# EXT-PHY.net
KiCad netlist of a schematic drawn in EAGLE
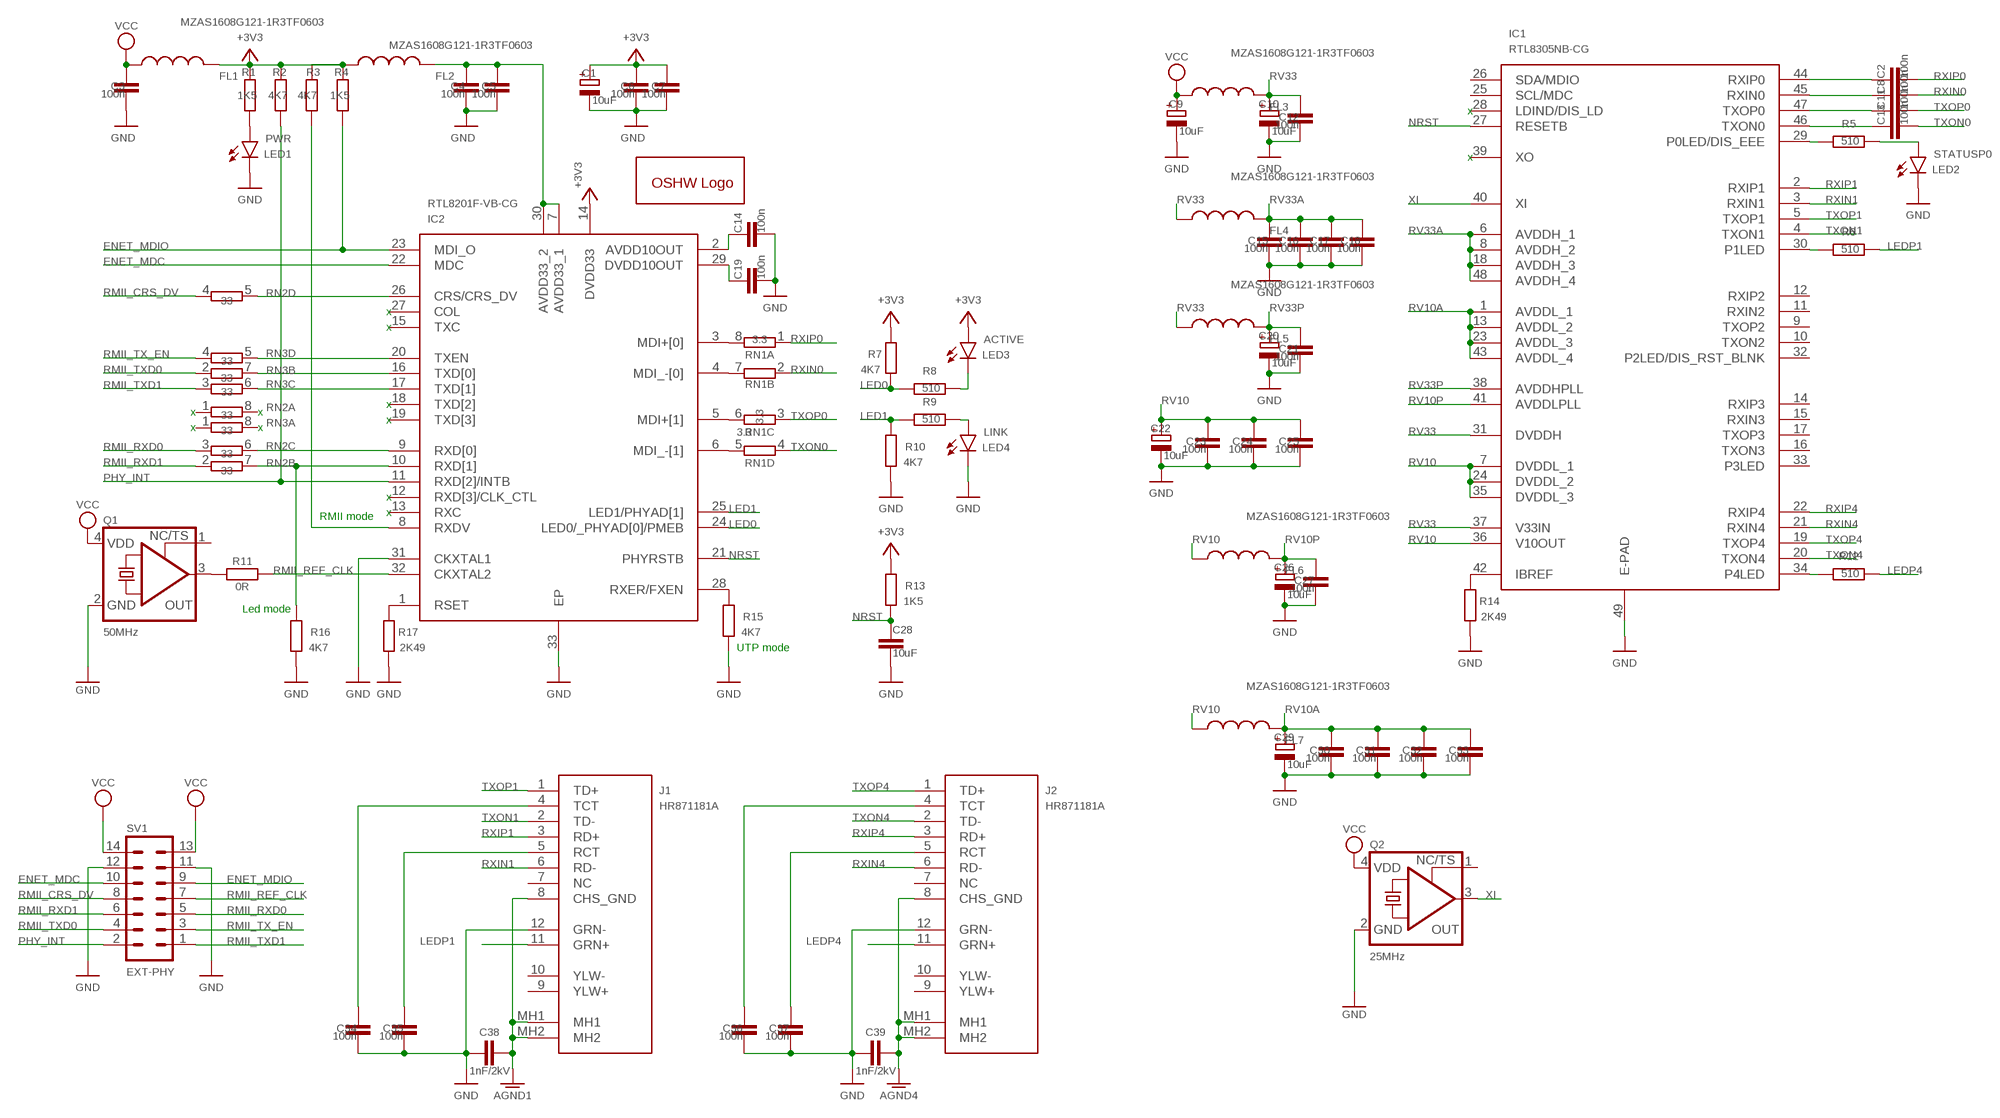
[diagram p0: schematic, sheet 1]

(export (version "E")
  (design (tool "Eeschema 10.0.6"))
  (components
    (comp (ref "C1")
      (value "10uF")
      (footprint "eagle-import:A_3216-18R")
      (libsource (lib "eagle-import") (part "CPOL-EUA/3216-18R"))
    )
    (comp (ref "C2")
      (value "100n")
      (footprint "eagle-import:C0402")
      (libsource (lib "eagle-import") (part "C-EUC0402"))
    )
    (comp (ref "C3")
      (value "100n")
      (footprint "eagle-import:C0402")
      (libsource (lib "eagle-import") (part "C-EUC0402"))
    )
    (comp (ref "C4")
      (value "100n")
      (footprint "eagle-import:C0402")
      (libsource (lib "eagle-import") (part "C-EUC0402"))
    )
    (comp (ref "C5")
      (value "100n")
      (footprint "eagle-import:C0402")
      (libsource (lib "eagle-import") (part "C-EUC0402"))
    )
    (comp (ref "C6")
      (value "100n")
      (footprint "eagle-import:C0402")
      (libsource (lib "eagle-import") (part "C-EUC0402"))
    )
    (comp (ref "C7")
      (value "100n")
      (footprint "eagle-import:C0402")
      (libsource (lib "eagle-import") (part "C-EUC0402"))
    )
    (comp (ref "C8")
      (value "100n")
      (footprint "eagle-import:C0402")
      (libsource (lib "eagle-import") (part "C-EUC0402"))
    )
    (comp (ref "C9")
      (value "10uF")
      (footprint "eagle-import:A_3216-18R")
      (libsource (lib "eagle-import") (part "CPOL-EUA/3216-18R"))
    )
    (comp (ref "C10")
      (value "10uF")
      (footprint "eagle-import:A_3216-18R")
      (libsource (lib "eagle-import") (part "CPOL-EUA/3216-18R"))
    )
    (comp (ref "C11")
      (value "100n")
      (footprint "eagle-import:C0402")
      (libsource (lib "eagle-import") (part "C-EUC0402"))
    )
    (comp (ref "C12")
      (value "100n")
      (footprint "eagle-import:C0402")
      (libsource (lib "eagle-import") (part "C-EUC0402"))
    )
    (comp (ref "C13")
      (value "100n")
      (footprint "eagle-import:C0402")
      (libsource (lib "eagle-import") (part "C-EUC0402"))
    )
    (comp (ref "C14")
      (value "100n")
      (footprint "eagle-import:C0402")
      (libsource (lib "eagle-import") (part "C-EUC0402"))
    )
    (comp (ref "C15")
      (value "100n")
      (footprint "eagle-import:C0402")
      (libsource (lib "eagle-import") (part "C-EUC0402"))
    )
    (comp (ref "C16")
      (value "100n")
      (footprint "eagle-import:C0402")
      (libsource (lib "eagle-import") (part "C-EUC0402"))
    )
    (comp (ref "C17")
      (value "100n")
      (footprint "eagle-import:C0402")
      (libsource (lib "eagle-import") (part "C-EUC0402"))
    )
    (comp (ref "C18")
      (value "100n")
      (footprint "eagle-import:C0402")
      (libsource (lib "eagle-import") (part "C-EUC0402"))
    )
    (comp (ref "C19")
      (value "100n")
      (footprint "eagle-import:C0402")
      (libsource (lib "eagle-import") (part "C-EUC0402"))
    )
    (comp (ref "C20")
      (value "10uF")
      (footprint "eagle-import:A_3216-18R")
      (libsource (lib "eagle-import") (part "CPOL-EUA/3216-18R"))
    )
    (comp (ref "C21")
      (value "100n")
      (footprint "eagle-import:C0402")
      (libsource (lib "eagle-import") (part "C-EUC0402"))
    )
    (comp (ref "C22")
      (value "10uF")
      (footprint "eagle-import:A_3216-18R")
      (libsource (lib "eagle-import") (part "CPOL-EUA/3216-18R"))
    )
    (comp (ref "C23")
      (value "100n")
      (footprint "eagle-import:C0402")
      (libsource (lib "eagle-import") (part "C-EUC0402"))
    )
    (comp (ref "C24")
      (value "100n")
      (footprint "eagle-import:C0402")
      (libsource (lib "eagle-import") (part "C-EUC0402"))
    )
    (comp (ref "C25")
      (value "100n")
      (footprint "eagle-import:C0402")
      (libsource (lib "eagle-import") (part "C-EUC0402"))
    )
    (comp (ref "C26")
      (value "10uF")
      (footprint "eagle-import:A_3216-18R")
      (libsource (lib "eagle-import") (part "CPOL-EUA/3216-18R"))
    )
    (comp (ref "C27")
      (value "100n")
      (footprint "eagle-import:C0402")
      (libsource (lib "eagle-import") (part "C-EUC0402"))
    )
    (comp (ref "C28")
      (value "10uF")
      (footprint "eagle-import:C0603")
      (libsource (lib "eagle-import") (part "C-EUC0603"))
    )
    (comp (ref "C29")
      (value "10uF")
      (footprint "eagle-import:A_3216-18R")
      (libsource (lib "eagle-import") (part "CPOL-EUA/3216-18R"))
    )
    (comp (ref "C30")
      (value "100n")
      (footprint "eagle-import:C0402")
      (libsource (lib "eagle-import") (part "C-EUC0402"))
    )
    (comp (ref "C31")
      (value "100n")
      (footprint "eagle-import:C0402")
      (libsource (lib "eagle-import") (part "C-EUC0402"))
    )
    (comp (ref "C32")
      (value "100n")
      (footprint "eagle-import:C0402")
      (libsource (lib "eagle-import") (part "C-EUC0402"))
    )
    (comp (ref "C33")
      (value "100n")
      (footprint "eagle-import:C0402")
      (libsource (lib "eagle-import") (part "C-EUC0402"))
    )
    (comp (ref "C34")
      (value "100n")
      (footprint "eagle-import:C0402")
      (libsource (lib "eagle-import") (part "C-EUC0402"))
    )
    (comp (ref "C35")
      (value "100n")
      (footprint "eagle-import:C0402")
      (libsource (lib "eagle-import") (part "C-EUC0402"))
    )
    (comp (ref "C36")
      (value "100n")
      (footprint "eagle-import:C0402")
      (libsource (lib "eagle-import") (part "C-EUC0402"))
    )
    (comp (ref "C37")
      (value "100n")
      (footprint "eagle-import:C0402")
      (libsource (lib "eagle-import") (part "C-EUC0402"))
    )
    (comp (ref "C38")
      (value "1nF/2kV")
      (footprint "eagle-import:C1206")
      (fields (field (name "SPICEPREFIX") "C"))
      (libsource (lib "eagle-import") (part "C-EUC1206"))
    )
    (comp (ref "C39")
      (value "1nF/2kV")
      (footprint "eagle-import:C1206")
      (fields (field (name "SPICEPREFIX") "C"))
      (libsource (lib "eagle-import") (part "C-EUC1206"))
    )
    (comp (ref "FL1")
      (value "MZAS1608G121-1R3TF0603")
      (footprint "eagle-import:0603")
      (libsource (lib "eagle-import") (part "MZAS1608G121-1R3TF0603"))
    )
    (comp (ref "FL2")
      (value "MZAS1608G121-1R3TF0603")
      (footprint "eagle-import:0603")
      (libsource (lib "eagle-import") (part "MZAS1608G121-1R3TF0603"))
    )
    (comp (ref "FL3")
      (value "MZAS1608G121-1R3TF0603")
      (footprint "eagle-import:0603")
      (libsource (lib "eagle-import") (part "MZAS1608G121-1R3TF0603"))
    )
    (comp (ref "FL4")
      (value "MZAS1608G121-1R3TF0603")
      (footprint "eagle-import:0603")
      (libsource (lib "eagle-import") (part "MZAS1608G121-1R3TF0603"))
    )
    (comp (ref "FL5")
      (value "MZAS1608G121-1R3TF0603")
      (footprint "eagle-import:0603")
      (libsource (lib "eagle-import") (part "MZAS1608G121-1R3TF0603"))
    )
    (comp (ref "FL6")
      (value "MZAS1608G121-1R3TF0603")
      (footprint "eagle-import:0603")
      (libsource (lib "eagle-import") (part "MZAS1608G121-1R3TF0603"))
    )
    (comp (ref "FL7")
      (value "MZAS1608G121-1R3TF0603")
      (footprint "eagle-import:0603")
      (libsource (lib "eagle-import") (part "MZAS1608G121-1R3TF0603"))
    )
    (comp (ref "GOLD_ORB_SM1")
      (value "OSHWLOGOLOGO5MM")
      (footprint "eagle-import:OSHW_5MM")
      (libsource (lib "eagle-import") (part "OSHWLOGOLOGO5MM"))
    )
    (comp (ref "IC1")
      (value "RTL8305NB-CG")
      (footprint "eagle-import:QFN40P600X600X100-49N")
      (libsource (lib "eagle-import") (part "RTL8305NB-CG"))
    )
    (comp (ref "IC2")
      (value "RTL8201F-VB-CG")
      (footprint "eagle-import:QFN50P500X500X100-33N")
      (fields (field (name "JLCPCB") "C45044"))
      (libsource (lib "eagle-import") (part "RTL8201F-VB-CG"))
    )
    (comp (ref "J1")
      (value "HR871181A")
      (footprint "eagle-import:HR871181A")
      (libsource (lib "eagle-import") (part "HR871181A"))
    )
    (comp (ref "J2")
      (value "HR871181A")
      (footprint "eagle-import:HR871181A")
      (libsource (lib "eagle-import") (part "HR871181A"))
    )
    (comp (ref "LED1")
      (value "PWR")
      (footprint "eagle-import:CHIP-LED0603")
      (libsource (lib "eagle-import") (part "LEDCHIP-LED0603"))
    )
    (comp (ref "LED2")
      (value "STATUSP0")
      (footprint "eagle-import:CHIP-LED0603")
      (libsource (lib "eagle-import") (part "LEDCHIP-LED0603"))
    )
    (comp (ref "LED3")
      (value "ACTIVE")
      (footprint "eagle-import:CHIP-LED0603")
      (libsource (lib "eagle-import") (part "LEDCHIP-LED0603"))
    )
    (comp (ref "LED4")
      (value "LINK")
      (footprint "eagle-import:CHIP-LED0603")
      (libsource (lib "eagle-import") (part "LEDCHIP-LED0603"))
    )
    (comp (ref "Q1")
      (value "50MHz")
      (footprint "eagle-import:3.2X2.5_KXO-V96")
      (libsource (lib "eagle-import") (part "KXO-PXO/XO-V96"))
    )
    (comp (ref "Q2")
      (value "25MHz")
      (footprint "eagle-import:3.2X2.5_KXO-V96")
      (libsource (lib "eagle-import") (part "KXO-PXO/XO-V96"))
    )
    (comp (ref "R1")
      (value "1K5")
      (footprint "eagle-import:R0603")
      (libsource (lib "eagle-import") (part "R-EU_R0603"))
    )
    (comp (ref "R2")
      (value "4K7")
      (footprint "eagle-import:R0603")
      (libsource (lib "eagle-import") (part "R-EU_R0603"))
    )
    (comp (ref "R3")
      (value "4K7")
      (footprint "eagle-import:R0603")
      (libsource (lib "eagle-import") (part "R-EU_R0603"))
    )
    (comp (ref "R4")
      (value "1K5")
      (footprint "eagle-import:R0603")
      (libsource (lib "eagle-import") (part "R-EU_R0603"))
    )
    (comp (ref "R5")
      (value "510")
      (footprint "eagle-import:R0603")
      (libsource (lib "eagle-import") (part "R-EU_R0603"))
    )
    (comp (ref "R6")
      (value "510")
      (footprint "eagle-import:R0603")
      (libsource (lib "eagle-import") (part "R-EU_R0603"))
    )
    (comp (ref "R7")
      (value "4K7")
      (footprint "eagle-import:R0603")
      (libsource (lib "eagle-import") (part "R-EU_R0603"))
    )
    (comp (ref "R8")
      (value "510")
      (footprint "eagle-import:R0603")
      (libsource (lib "eagle-import") (part "R-EU_R0603"))
    )
    (comp (ref "R9")
      (value "510")
      (footprint "eagle-import:R0603")
      (libsource (lib "eagle-import") (part "R-EU_R0603"))
    )
    (comp (ref "R10")
      (value "4K7")
      (footprint "eagle-import:R0603")
      (libsource (lib "eagle-import") (part "R-EU_R0603"))
    )
    (comp (ref "R11")
      (value "0R")
      (footprint "eagle-import:R0603")
      (libsource (lib "eagle-import") (part "R-EU_R0603"))
    )
    (comp (ref "R12")
      (value "510")
      (footprint "eagle-import:R0603")
      (libsource (lib "eagle-import") (part "R-EU_R0603"))
    )
    (comp (ref "R13")
      (value "1K5")
      (footprint "eagle-import:R0603")
      (libsource (lib "eagle-import") (part "R-EU_R0603"))
    )
    (comp (ref "R14")
      (value "2K49")
      (footprint "eagle-import:R0603")
      (libsource (lib "eagle-import") (part "R-EU_R0603"))
    )
    (comp (ref "R15")
      (value "4K7")
      (footprint "eagle-import:R0603")
      (libsource (lib "eagle-import") (part "R-EU_R0603"))
    )
    (comp (ref "R16")
      (value "4K7")
      (footprint "eagle-import:R0603")
      (libsource (lib "eagle-import") (part "R-EU_R0603"))
    )
    (comp (ref "R17")
      (value "2K49")
      (footprint "eagle-import:R0603")
      (libsource (lib "eagle-import") (part "R-EU_R0603"))
    )
    (comp (ref "RN1")
      (value "3.3")
      (footprint "eagle-import:4X0402ARV341")
      (fields (field (name "JLCPCB") "C728736"))
      (libsource (lib "eagle-import") (part "4R-N0402ARV341"))
    )
    (comp (ref "RN2")
      (value "33")
      (footprint "eagle-import:4X0402ARV341")
      (fields (field (name "JLCPCB") "C25501"))
      (libsource (lib "eagle-import") (part "4R-N0402ARV341"))
    )
    (comp (ref "RN3")
      (value "33")
      (footprint "eagle-import:4X0402ARV341")
      (fields (field (name "JLCPCB") "C25501"))
      (libsource (lib "eagle-import") (part "4R-N0402ARV341"))
    )
    (comp (ref "SV1")
      (value "EXT-PHY")
      (footprint "eagle-import:MA07-2W")
      (libsource (lib "eagle-import") (part "MA07-2W"))
    )
  )
  (nets
    (net (code "1") (name "+3V3") (class "Default")
      (node (ref "C1") (pin "+") (pinfunction "+_+") (pintype "passive"))
      (node (ref "C6") (pin "2") (pinfunction "2_2") (pintype "passive"))
      (node (ref "C7") (pin "2") (pinfunction "2_2") (pintype "passive"))
      (node (ref "FL1") (pin "2") (pinfunction "2_2") (pintype "passive"))
      (node (ref "FL2") (pin "1") (pinfunction "1_1") (pintype "passive"))
      (node (ref "IC2") (pin "14") (pinfunction "DVDD33_14") (pintype "bidirectional"))
      (node (ref "LED3") (pin "A") (pinfunction "A_A") (pintype "passive"))
      (node (ref "R1") (pin "2") (pinfunction "2_2") (pintype "passive"))
      (node (ref "R13") (pin "2") (pinfunction "2_2") (pintype "passive"))
      (node (ref "R2") (pin "2") (pinfunction "2_2") (pintype "passive"))
      (node (ref "R3") (pin "1") (pinfunction "1_1") (pintype "passive"))
      (node (ref "R4") (pin "2") (pinfunction "2_2") (pintype "passive"))
      (node (ref "R7") (pin "2") (pinfunction "2_2") (pintype "passive"))
    )
    (net (code "2") (name "/ENET_MDC") (class "Default")
      (node (ref "IC2") (pin "22") (pinfunction "MDC_22") (pintype "bidirectional"))
      (node (ref "SV1") (pin "10") (pinfunction "10_10") (pintype "passive"))
    )
    (net (code "3") (name "/ENET_MDIO") (class "Default")
      (node (ref "IC2") (pin "23") (pinfunction "MDI_O_23") (pintype "bidirectional"))
      (node (ref "R4") (pin "1") (pinfunction "1_1") (pintype "passive"))
      (node (ref "SV1") (pin "9") (pinfunction "9_9") (pintype "passive"))
    )
    (net (code "4") (name "/LED0") (class "Default")
      (node (ref "IC2") (pin "24") (pinfunction "LED0/_PHYAD[0]/PMEB_24") (pintype "bidirectional"))
      (node (ref "R7") (pin "1") (pinfunction "1_1") (pintype "passive"))
      (node (ref "R8") (pin "2") (pinfunction "2_2") (pintype "passive"))
    )
    (net (code "5") (name "/LED1") (class "Default")
      (node (ref "IC2") (pin "25") (pinfunction "LED1/PHYAD[1]_25") (pintype "bidirectional"))
      (node (ref "R10") (pin "2") (pinfunction "2_2") (pintype "passive"))
      (node (ref "R9") (pin "2") (pinfunction "2_2") (pintype "passive"))
    )
    (net (code "6") (name "/LEDP1") (class "Default")
      (node (ref "J1") (pin "11") (pinfunction "GRN+_11") (pintype "bidirectional"))
      (node (ref "R6") (pin "1") (pinfunction "1_1") (pintype "passive"))
    )
    (net (code "7") (name "/LEDP4") (class "Default")
      (node (ref "J2") (pin "11") (pinfunction "GRN+_11") (pintype "bidirectional"))
      (node (ref "R12") (pin "1") (pinfunction "1_1") (pintype "passive"))
    )
    (net (code "8") (name "/NRST") (class "Default")
      (node (ref "C28") (pin "1") (pinfunction "1_1") (pintype "passive"))
      (node (ref "IC1") (pin "27") (pinfunction "RESETB_27") (pintype "input"))
      (node (ref "IC2") (pin "21") (pinfunction "PHYRSTB_21") (pintype "bidirectional"))
      (node (ref "R13") (pin "1") (pinfunction "1_1") (pintype "passive"))
    )
    (net (code "9") (name "/PHY_INT") (class "Default")
      (node (ref "IC2") (pin "11") (pinfunction "RXD[2]/INTB_11") (pintype "bidirectional"))
      (node (ref "R2") (pin "1") (pinfunction "1_1") (pintype "passive"))
      (node (ref "SV1") (pin "2") (pinfunction "2_2") (pintype "passive"))
    )
    (net (code "10") (name "/RMII_CRS_DV") (class "Default")
      (node (ref "RN2") (pin "4") (pinfunction "1_4") (pintype "passive"))
      (node (ref "SV1") (pin "8") (pinfunction "8_8") (pintype "passive"))
    )
    (net (code "11") (name "/RMII_REF_CLK") (class "Default")
      (node (ref "IC2") (pin "32") (pinfunction "CKXTAL2_32") (pintype "bidirectional"))
      (node (ref "R11") (pin "2") (pinfunction "2_2") (pintype "passive"))
      (node (ref "SV1") (pin "7") (pinfunction "7_7") (pintype "passive"))
    )
    (net (code "12") (name "/RMII_RXD0") (class "Default")
      (node (ref "RN2") (pin "3") (pinfunction "1_3") (pintype "passive"))
      (node (ref "SV1") (pin "5") (pinfunction "5_5") (pintype "passive"))
    )
    (net (code "13") (name "/RMII_RXD1") (class "Default")
      (node (ref "RN2") (pin "2") (pinfunction "1_2") (pintype "passive"))
      (node (ref "SV1") (pin "6") (pinfunction "6_6") (pintype "passive"))
    )
    (net (code "14") (name "/RMII_TXD0") (class "Default")
      (node (ref "RN3") (pin "2") (pinfunction "1_2") (pintype "passive"))
      (node (ref "SV1") (pin "4") (pinfunction "4_4") (pintype "passive"))
    )
    (net (code "15") (name "/RMII_TXD1") (class "Default")
      (node (ref "RN3") (pin "3") (pinfunction "1_3") (pintype "passive"))
      (node (ref "SV1") (pin "1") (pinfunction "1_1") (pintype "passive"))
    )
    (net (code "16") (name "/RMII_TX_EN") (class "Default")
      (node (ref "RN3") (pin "4") (pinfunction "1_4") (pintype "passive"))
      (node (ref "SV1") (pin "3") (pinfunction "3_3") (pintype "passive"))
    )
    (net (code "17") (name "/RV10") (class "Default")
      (node (ref "C22") (pin "+") (pinfunction "+_+") (pintype "passive"))
      (node (ref "C23") (pin "2") (pinfunction "2_2") (pintype "passive"))
      (node (ref "C24") (pin "2") (pinfunction "2_2") (pintype "passive"))
      (node (ref "C25") (pin "2") (pinfunction "2_2") (pintype "passive"))
      (node (ref "FL6") (pin "1") (pinfunction "1_1") (pintype "passive"))
      (node (ref "FL7") (pin "1") (pinfunction "1_1") (pintype "passive"))
      (node (ref "IC1") (pin "24") (pinfunction "DVDDL_2_24") (pintype "power_in"))
      (node (ref "IC1") (pin "35") (pinfunction "DVDDL_3_35") (pintype "power_in"))
      (node (ref "IC1") (pin "36") (pinfunction "V10OUT_36") (pintype "power_in"))
      (node (ref "IC1") (pin "7") (pinfunction "DVDDL_1_7") (pintype "power_in"))
    )
    (net (code "18") (name "/RV10A") (class "Default")
      (node (ref "C29") (pin "+") (pinfunction "+_+") (pintype "passive"))
      (node (ref "C30") (pin "2") (pinfunction "2_2") (pintype "passive"))
      (node (ref "C31") (pin "2") (pinfunction "2_2") (pintype "passive"))
      (node (ref "C32") (pin "2") (pinfunction "2_2") (pintype "passive"))
      (node (ref "C33") (pin "2") (pinfunction "2_2") (pintype "passive"))
      (node (ref "FL7") (pin "2") (pinfunction "2_2") (pintype "passive"))
      (node (ref "IC1") (pin "1") (pinfunction "AVDDL_1_1") (pintype "power_in"))
      (node (ref "IC1") (pin "13") (pinfunction "AVDDL_2_13") (pintype "power_in"))
      (node (ref "IC1") (pin "23") (pinfunction "AVDDL_3_23") (pintype "power_in"))
      (node (ref "IC1") (pin "43") (pinfunction "AVDDL_4_43") (pintype "power_in"))
    )
    (net (code "19") (name "/RV10P") (class "Default")
      (node (ref "C26") (pin "+") (pinfunction "+_+") (pintype "passive"))
      (node (ref "C27") (pin "2") (pinfunction "2_2") (pintype "passive"))
      (node (ref "FL6") (pin "2") (pinfunction "2_2") (pintype "passive"))
      (node (ref "IC1") (pin "41") (pinfunction "AVDDLPLL_41") (pintype "power_in"))
    )
    (net (code "20") (name "/RV33") (class "Default")
      (node (ref "C10") (pin "+") (pinfunction "+_+") (pintype "passive"))
      (node (ref "C12") (pin "2") (pinfunction "2_2") (pintype "passive"))
      (node (ref "FL3") (pin "2") (pinfunction "2_2") (pintype "passive"))
      (node (ref "FL4") (pin "1") (pinfunction "1_1") (pintype "passive"))
      (node (ref "FL5") (pin "1") (pinfunction "1_1") (pintype "passive"))
      (node (ref "IC1") (pin "31") (pinfunction "DVDDH_31") (pintype "power_in"))
      (node (ref "IC1") (pin "37") (pinfunction "V33IN_37") (pintype "power_in"))
    )
    (net (code "21") (name "/RV33A") (class "Default")
      (node (ref "C15") (pin "2") (pinfunction "2_2") (pintype "passive"))
      (node (ref "C16") (pin "2") (pinfunction "2_2") (pintype "passive"))
      (node (ref "C17") (pin "2") (pinfunction "2_2") (pintype "passive"))
      (node (ref "C18") (pin "2") (pinfunction "2_2") (pintype "passive"))
      (node (ref "FL4") (pin "2") (pinfunction "2_2") (pintype "passive"))
      (node (ref "IC1") (pin "18") (pinfunction "AVDDH_3_18") (pintype "power_in"))
      (node (ref "IC1") (pin "48") (pinfunction "AVDDH_4_48") (pintype "power_in"))
      (node (ref "IC1") (pin "6") (pinfunction "AVDDH_1_6") (pintype "power_in"))
      (node (ref "IC1") (pin "8") (pinfunction "AVDDH_2_8") (pintype "power_in"))
    )
    (net (code "22") (name "/RV33P") (class "Default")
      (node (ref "C20") (pin "+") (pinfunction "+_+") (pintype "passive"))
      (node (ref "C21") (pin "2") (pinfunction "2_2") (pintype "passive"))
      (node (ref "FL5") (pin "2") (pinfunction "2_2") (pintype "passive"))
      (node (ref "IC1") (pin "38") (pinfunction "AVDDHPLL_38") (pintype "power_in"))
    )
    (net (code "23") (name "/RXIN0") (class "Default")
      (node (ref "C8") (pin "2") (pinfunction "2_2") (pintype "passive"))
      (node (ref "RN1") (pin "2") (pinfunction "1_2") (pintype "passive"))
    )
    (net (code "24") (name "/RXIN1") (class "Default")
      (node (ref "IC1") (pin "3") (pinfunction "RXIN1_3") (pintype "input"))
      (node (ref "J1") (pin "6") (pinfunction "RD-_6") (pintype "bidirectional"))
    )
    (net (code "25") (name "/RXIN4") (class "Default")
      (node (ref "IC1") (pin "21") (pinfunction "RXIN4_21") (pintype "input"))
      (node (ref "J2") (pin "6") (pinfunction "RD-_6") (pintype "bidirectional"))
    )
    (net (code "26") (name "/RXIP0") (class "Default")
      (node (ref "C2") (pin "2") (pinfunction "2_2") (pintype "passive"))
      (node (ref "RN1") (pin "1") (pinfunction "1_1") (pintype "passive"))
    )
    (net (code "27") (name "/RXIP1") (class "Default")
      (node (ref "IC1") (pin "2") (pinfunction "RXIP1_2") (pintype "input"))
      (node (ref "J1") (pin "3") (pinfunction "RD+_3") (pintype "bidirectional"))
    )
    (net (code "28") (name "/RXIP4") (class "Default")
      (node (ref "IC1") (pin "22") (pinfunction "RXIP4_22") (pintype "input"))
      (node (ref "J2") (pin "3") (pinfunction "RD+_3") (pintype "bidirectional"))
    )
    (net (code "29") (name "/TXON0") (class "Default")
      (node (ref "C13") (pin "2") (pinfunction "2_2") (pintype "passive"))
      (node (ref "RN1") (pin "4") (pinfunction "1_4") (pintype "passive"))
    )
    (net (code "30") (name "/TXON1") (class "Default")
      (node (ref "IC1") (pin "4") (pinfunction "TXON1_4") (pintype "output"))
      (node (ref "J1") (pin "2") (pinfunction "TD-_2") (pintype "bidirectional"))
    )
    (net (code "31") (name "/TXON4") (class "Default")
      (node (ref "IC1") (pin "20") (pinfunction "TXON4_20") (pintype "output"))
      (node (ref "J2") (pin "2") (pinfunction "TD-_2") (pintype "bidirectional"))
    )
    (net (code "32") (name "/TXOP0") (class "Default")
      (node (ref "C11") (pin "2") (pinfunction "2_2") (pintype "passive"))
      (node (ref "RN1") (pin "3") (pinfunction "1_3") (pintype "passive"))
    )
    (net (code "33") (name "/TXOP1") (class "Default")
      (node (ref "IC1") (pin "5") (pinfunction "TXOP1_5") (pintype "output"))
      (node (ref "J1") (pin "1") (pinfunction "TD+_1") (pintype "bidirectional"))
    )
    (net (code "34") (name "/TXOP4") (class "Default")
      (node (ref "IC1") (pin "19") (pinfunction "TXOP4_19") (pintype "output"))
      (node (ref "J2") (pin "1") (pinfunction "TD+_1") (pintype "bidirectional"))
    )
    (net (code "35") (name "/XI") (class "Default")
      (node (ref "IC1") (pin "40") (pinfunction "XI_40") (pintype "input"))
      (node (ref "Q2") (pin "3") (pinfunction "OUT_3") (pintype "output"))
    )
    (net (code "36") (name "AGND1") (class "Default")
      (node (ref "C38") (pin "2") (pinfunction "2_2") (pintype "passive"))
      (node (ref "J1") (pin "8") (pinfunction "CHS_GND_8") (pintype "bidirectional"))
      (node (ref "J1") (pin "MH1") (pinfunction "MH1_MH1") (pintype "bidirectional"))
      (node (ref "J1") (pin "MH2") (pinfunction "MH2_MH2") (pintype "bidirectional"))
    )
    (net (code "37") (name "AGND4") (class "Default")
      (node (ref "C39") (pin "2") (pinfunction "2_2") (pintype "passive"))
      (node (ref "J2") (pin "8") (pinfunction "CHS_GND_8") (pintype "bidirectional"))
      (node (ref "J2") (pin "MH1") (pinfunction "MH1_MH1") (pintype "bidirectional"))
      (node (ref "J2") (pin "MH2") (pinfunction "MH2_MH2") (pintype "bidirectional"))
    )
    (net (code "38") (name "GND") (class "Default")
      (node (ref "C1") (pin "-") (pinfunction "-_-") (pintype "passive"))
      (node (ref "C10") (pin "-") (pinfunction "-_-") (pintype "passive"))
      (node (ref "C12") (pin "1") (pinfunction "1_1") (pintype "passive"))
      (node (ref "C14") (pin "2") (pinfunction "2_2") (pintype "passive"))
      (node (ref "C15") (pin "1") (pinfunction "1_1") (pintype "passive"))
      (node (ref "C16") (pin "1") (pinfunction "1_1") (pintype "passive"))
      (node (ref "C17") (pin "1") (pinfunction "1_1") (pintype "passive"))
      (node (ref "C18") (pin "1") (pinfunction "1_1") (pintype "passive"))
      (node (ref "C19") (pin "2") (pinfunction "2_2") (pintype "passive"))
      (node (ref "C20") (pin "-") (pinfunction "-_-") (pintype "passive"))
      (node (ref "C21") (pin "1") (pinfunction "1_1") (pintype "passive"))
      (node (ref "C22") (pin "-") (pinfunction "-_-") (pintype "passive"))
      (node (ref "C23") (pin "1") (pinfunction "1_1") (pintype "passive"))
      (node (ref "C24") (pin "1") (pinfunction "1_1") (pintype "passive"))
      (node (ref "C25") (pin "1") (pinfunction "1_1") (pintype "passive"))
      (node (ref "C26") (pin "-") (pinfunction "-_-") (pintype "passive"))
      (node (ref "C27") (pin "1") (pinfunction "1_1") (pintype "passive"))
      (node (ref "C28") (pin "2") (pinfunction "2_2") (pintype "passive"))
      (node (ref "C29") (pin "-") (pinfunction "-_-") (pintype "passive"))
      (node (ref "C3") (pin "1") (pinfunction "1_1") (pintype "passive"))
      (node (ref "C30") (pin "1") (pinfunction "1_1") (pintype "passive"))
      (node (ref "C31") (pin "1") (pinfunction "1_1") (pintype "passive"))
      (node (ref "C32") (pin "1") (pinfunction "1_1") (pintype "passive"))
      (node (ref "C33") (pin "1") (pinfunction "1_1") (pintype "passive"))
      (node (ref "C34") (pin "1") (pinfunction "1_1") (pintype "passive"))
      (node (ref "C35") (pin "1") (pinfunction "1_1") (pintype "passive"))
      (node (ref "C36") (pin "1") (pinfunction "1_1") (pintype "passive"))
      (node (ref "C37") (pin "1") (pinfunction "1_1") (pintype "passive"))
      (node (ref "C38") (pin "1") (pinfunction "1_1") (pintype "passive"))
      (node (ref "C39") (pin "1") (pinfunction "1_1") (pintype "passive"))
      (node (ref "C4") (pin "1") (pinfunction "1_1") (pintype "passive"))
      (node (ref "C5") (pin "1") (pinfunction "1_1") (pintype "passive"))
      (node (ref "C6") (pin "1") (pinfunction "1_1") (pintype "passive"))
      (node (ref "C7") (pin "1") (pinfunction "1_1") (pintype "passive"))
      (node (ref "C9") (pin "-") (pinfunction "-_-") (pintype "passive"))
      (node (ref "IC1") (pin "49") (pinfunction "E-PAD_49") (pintype "power_in"))
      (node (ref "IC2") (pin "31") (pinfunction "CKXTAL1_31") (pintype "bidirectional"))
      (node (ref "IC2") (pin "33") (pinfunction "EP_33") (pintype "bidirectional"))
      (node (ref "J1") (pin "12") (pinfunction "GRN-_12") (pintype "bidirectional"))
      (node (ref "J2") (pin "12") (pinfunction "GRN-_12") (pintype "bidirectional"))
      (node (ref "LED1") (pin "C") (pinfunction "C_C") (pintype "passive"))
      (node (ref "LED2") (pin "C") (pinfunction "C_C") (pintype "passive"))
      (node (ref "LED4") (pin "C") (pinfunction "C_C") (pintype "passive"))
      (node (ref "Q1") (pin "2") (pinfunction "GND_2") (pintype "power_in"))
      (node (ref "Q2") (pin "2") (pinfunction "GND_2") (pintype "power_in"))
      (node (ref "R10") (pin "1") (pinfunction "1_1") (pintype "passive"))
      (node (ref "R14") (pin "2") (pinfunction "2_2") (pintype "passive"))
      (node (ref "R15") (pin "1") (pinfunction "1_1") (pintype "passive"))
      (node (ref "R16") (pin "1") (pinfunction "1_1") (pintype "passive"))
      (node (ref "R17") (pin "2") (pinfunction "2_2") (pintype "passive"))
      (node (ref "SV1") (pin "11") (pinfunction "11_11") (pintype "passive"))
      (node (ref "SV1") (pin "12") (pinfunction "12_12") (pintype "passive"))
    )
    (net (code "39") (name "Net-(IC1-IBREF)") (class "Default")
      (node (ref "IC1") (pin "42") (pinfunction "IBREF_42") (pintype "output"))
      (node (ref "R14") (pin "1") (pinfunction "1_1") (pintype "passive"))
    )
    (net (code "40") (name "Net-(IC1-P0LED{slash}DIS_EEE)") (class "Default")
      (node (ref "IC1") (pin "29") (pinfunction "P0LED/DIS_EEE_29") (pintype "bidirectional"))
      (node (ref "R5") (pin "2") (pinfunction "2_2") (pintype "passive"))
    )
    (net (code "41") (name "Net-(IC1-P1LED)") (class "Default")
      (node (ref "IC1") (pin "30") (pinfunction "P1LED_30") (pintype "bidirectional"))
      (node (ref "R6") (pin "2") (pinfunction "2_2") (pintype "passive"))
    )
    (net (code "42") (name "Net-(IC1-P4LED)") (class "Default")
      (node (ref "IC1") (pin "34") (pinfunction "P4LED_34") (pintype "bidirectional"))
      (node (ref "R12") (pin "2") (pinfunction "2_2") (pintype "passive"))
    )
    (net (code "43") (name "Net-(IC1-RXIN0)") (class "Default")
      (node (ref "C8") (pin "1") (pinfunction "1_1") (pintype "passive"))
      (node (ref "IC1") (pin "45") (pinfunction "RXIN0_45") (pintype "input"))
    )
    (net (code "44") (name "Net-(IC1-RXIP0)") (class "Default")
      (node (ref "C2") (pin "1") (pinfunction "1_1") (pintype "passive"))
      (node (ref "IC1") (pin "44") (pinfunction "RXIP0_44") (pintype "input"))
    )
    (net (code "45") (name "Net-(IC1-TXON0)") (class "Default")
      (node (ref "C13") (pin "1") (pinfunction "1_1") (pintype "passive"))
      (node (ref "IC1") (pin "46") (pinfunction "TXON0_46") (pintype "output"))
    )
    (net (code "46") (name "Net-(IC1-TXOP0)") (class "Default")
      (node (ref "C11") (pin "1") (pinfunction "1_1") (pintype "passive"))
      (node (ref "IC1") (pin "47") (pinfunction "TXOP0_47") (pintype "output"))
    )
    (net (code "47") (name "Net-(IC2-AVDD10OUT)") (class "Default")
      (node (ref "C14") (pin "1") (pinfunction "1_1") (pintype "passive"))
      (node (ref "IC2") (pin "2") (pinfunction "AVDD10OUT_2") (pintype "bidirectional"))
    )
    (net (code "48") (name "Net-(IC2-AVDD33_1)") (class "Default")
      (node (ref "C4") (pin "2") (pinfunction "2_2") (pintype "passive"))
      (node (ref "C5") (pin "2") (pinfunction "2_2") (pintype "passive"))
      (node (ref "FL2") (pin "2") (pinfunction "2_2") (pintype "passive"))
      (node (ref "IC2") (pin "30") (pinfunction "AVDD33_2_30") (pintype "bidirectional"))
      (node (ref "IC2") (pin "7") (pinfunction "AVDD33_1_7") (pintype "bidirectional"))
    )
    (net (code "49") (name "Net-(IC2-CRS{slash}CRS_DV)") (class "Default")
      (node (ref "IC2") (pin "26") (pinfunction "CRS/CRS_DV_26") (pintype "bidirectional"))
      (node (ref "RN2") (pin "5") (pinfunction "2_5") (pintype "passive"))
    )
    (net (code "50") (name "Net-(IC2-DVDD10OUT)") (class "Default")
      (node (ref "C19") (pin "1") (pinfunction "1_1") (pintype "passive"))
      (node (ref "IC2") (pin "29") (pinfunction "DVDD10OUT_29") (pintype "bidirectional"))
    )
    (net (code "51") (name "Net-(IC2-MDI+[0])") (class "Default")
      (node (ref "IC2") (pin "3") (pinfunction "MDI+[0]_3") (pintype "bidirectional"))
      (node (ref "RN1") (pin "8") (pinfunction "2_8") (pintype "passive"))
    )
    (net (code "52") (name "Net-(IC2-MDI+[1])") (class "Default")
      (node (ref "IC2") (pin "5") (pinfunction "MDI+[1]_5") (pintype "bidirectional"))
      (node (ref "RN1") (pin "6") (pinfunction "2_6") (pintype "passive"))
    )
    (net (code "53") (name "Net-(IC2-MDI_-[0])") (class "Default")
      (node (ref "IC2") (pin "4") (pinfunction "MDI_-[0]_4") (pintype "bidirectional"))
      (node (ref "RN1") (pin "7") (pinfunction "2_7") (pintype "passive"))
    )
    (net (code "54") (name "Net-(IC2-MDI_-[1])") (class "Default")
      (node (ref "IC2") (pin "6") (pinfunction "MDI_-[1]_6") (pintype "bidirectional"))
      (node (ref "RN1") (pin "5") (pinfunction "2_5") (pintype "passive"))
    )
    (net (code "55") (name "Net-(IC2-RSET)") (class "Default")
      (node (ref "IC2") (pin "1") (pinfunction "RSET_1") (pintype "bidirectional"))
      (node (ref "R17") (pin "1") (pinfunction "1_1") (pintype "passive"))
    )
    (net (code "56") (name "Net-(IC2-RXDV)") (class "Default")
      (node (ref "IC2") (pin "8") (pinfunction "RXDV_8") (pintype "bidirectional"))
      (node (ref "R3") (pin "2") (pinfunction "2_2") (pintype "passive"))
    )
    (net (code "57") (name "Net-(IC2-RXD[0])") (class "Default")
      (node (ref "IC2") (pin "9") (pinfunction "RXD[0]_9") (pintype "bidirectional"))
      (node (ref "RN2") (pin "6") (pinfunction "2_6") (pintype "passive"))
    )
    (net (code "58") (name "Net-(IC2-RXD[1])") (class "Default")
      (node (ref "IC2") (pin "10") (pinfunction "RXD[1]_10") (pintype "bidirectional"))
      (node (ref "R16") (pin "2") (pinfunction "2_2") (pintype "passive"))
      (node (ref "RN2") (pin "7") (pinfunction "2_7") (pintype "passive"))
    )
    (net (code "59") (name "Net-(IC2-RXER{slash}FXEN)") (class "Default")
      (node (ref "IC2") (pin "28") (pinfunction "RXER/FXEN_28") (pintype "bidirectional"))
      (node (ref "R15") (pin "2") (pinfunction "2_2") (pintype "passive"))
    )
    (net (code "60") (name "Net-(IC2-TXD[0])") (class "Default")
      (node (ref "IC2") (pin "16") (pinfunction "TXD[0]_16") (pintype "bidirectional"))
      (node (ref "RN3") (pin "7") (pinfunction "2_7") (pintype "passive"))
    )
    (net (code "61") (name "Net-(IC2-TXD[1])") (class "Default")
      (node (ref "IC2") (pin "17") (pinfunction "TXD[1]_17") (pintype "bidirectional"))
      (node (ref "RN3") (pin "6") (pinfunction "2_6") (pintype "passive"))
    )
    (net (code "62") (name "Net-(IC2-TXEN)") (class "Default")
      (node (ref "IC2") (pin "20") (pinfunction "TXEN_20") (pintype "bidirectional"))
      (node (ref "RN3") (pin "5") (pinfunction "2_5") (pintype "passive"))
    )
    (net (code "63") (name "Net-(J1-RCT)") (class "Default")
      (node (ref "C35") (pin "2") (pinfunction "2_2") (pintype "passive"))
      (node (ref "J1") (pin "5") (pinfunction "RCT_5") (pintype "bidirectional"))
    )
    (net (code "64") (name "Net-(J1-TCT)") (class "Default")
      (node (ref "C34") (pin "2") (pinfunction "2_2") (pintype "passive"))
      (node (ref "J1") (pin "4") (pinfunction "TCT_4") (pintype "bidirectional"))
    )
    (net (code "65") (name "Net-(J2-RCT)") (class "Default")
      (node (ref "C37") (pin "2") (pinfunction "2_2") (pintype "passive"))
      (node (ref "J2") (pin "5") (pinfunction "RCT_5") (pintype "bidirectional"))
    )
    (net (code "66") (name "Net-(J2-TCT)") (class "Default")
      (node (ref "C36") (pin "2") (pinfunction "2_2") (pintype "passive"))
      (node (ref "J2") (pin "4") (pinfunction "TCT_4") (pintype "bidirectional"))
    )
    (net (code "67") (name "Net-(LED1-PadA)") (class "Default")
      (node (ref "LED1") (pin "A") (pinfunction "A_A") (pintype "passive"))
      (node (ref "R1") (pin "1") (pinfunction "1_1") (pintype "passive"))
    )
    (net (code "68") (name "Net-(LED2-PadA)") (class "Default")
      (node (ref "LED2") (pin "A") (pinfunction "A_A") (pintype "passive"))
      (node (ref "R5") (pin "1") (pinfunction "1_1") (pintype "passive"))
    )
    (net (code "69") (name "Net-(LED3-PadC)") (class "Default")
      (node (ref "LED3") (pin "C") (pinfunction "C_C") (pintype "passive"))
      (node (ref "R8") (pin "1") (pinfunction "1_1") (pintype "passive"))
    )
    (net (code "70") (name "Net-(LED4-PadA)") (class "Default")
      (node (ref "LED4") (pin "A") (pinfunction "A_A") (pintype "passive"))
      (node (ref "R9") (pin "1") (pinfunction "1_1") (pintype "passive"))
    )
    (net (code "71") (name "Net-(Q1-OUT)") (class "Default")
      (node (ref "Q1") (pin "3") (pinfunction "OUT_3") (pintype "output"))
      (node (ref "R11") (pin "1") (pinfunction "1_1") (pintype "passive"))
    )
    (net (code "72") (name "VCC") (class "Default")
      (node (ref "C3") (pin "2") (pinfunction "2_2") (pintype "passive"))
      (node (ref "C9") (pin "+") (pinfunction "+_+") (pintype "passive"))
      (node (ref "FL1") (pin "1") (pinfunction "1_1") (pintype "passive"))
      (node (ref "FL3") (pin "1") (pinfunction "1_1") (pintype "passive"))
      (node (ref "Q1") (pin "4") (pinfunction "VDD_4") (pintype "power_in"))
      (node (ref "Q2") (pin "4") (pinfunction "VDD_4") (pintype "power_in"))
      (node (ref "SV1") (pin "13") (pinfunction "13_13") (pintype "passive"))
      (node (ref "SV1") (pin "14") (pinfunction "14_14") (pintype "passive"))
    )
    (net (code "73") (name "unconnected-(IC1-LDIND{slash}DIS_LD-Pad28)") (class "Default")
      (node (ref "IC1") (pin "28") (pinfunction "LDIND/DIS_LD_28") (pintype "bidirectional"))
    )
    (net (code "74") (name "unconnected-(IC1-P2LED{slash}DIS_RST_BLNK-Pad32)") (class "Default")
      (node (ref "IC1") (pin "32") (pinfunction "P2LED/DIS_RST_BLNK_32") (pintype "bidirectional"))
    )
    (net (code "75") (name "unconnected-(IC1-P3LED-Pad33)") (class "Default")
      (node (ref "IC1") (pin "33") (pinfunction "P3LED_33") (pintype "bidirectional"))
    )
    (net (code "76") (name "unconnected-(IC1-RXIN2-Pad11)") (class "Default")
      (node (ref "IC1") (pin "11") (pinfunction "RXIN2_11") (pintype "input"))
    )
    (net (code "77") (name "unconnected-(IC1-RXIN3-Pad15)") (class "Default")
      (node (ref "IC1") (pin "15") (pinfunction "RXIN3_15") (pintype "input"))
    )
    (net (code "78") (name "unconnected-(IC1-RXIP2-Pad12)") (class "Default")
      (node (ref "IC1") (pin "12") (pinfunction "RXIP2_12") (pintype "input"))
    )
    (net (code "79") (name "unconnected-(IC1-RXIP3-Pad14)") (class "Default")
      (node (ref "IC1") (pin "14") (pinfunction "RXIP3_14") (pintype "input"))
    )
    (net (code "80") (name "unconnected-(IC1-SCL{slash}MDC-Pad25)") (class "Default")
      (node (ref "IC1") (pin "25") (pinfunction "SCL/MDC_25") (pintype "bidirectional"))
    )
    (net (code "81") (name "unconnected-(IC1-SDA{slash}MDIO-Pad26)") (class "Default")
      (node (ref "IC1") (pin "26") (pinfunction "SDA/MDIO_26") (pintype "bidirectional"))
    )
    (net (code "82") (name "unconnected-(IC1-TXON2-Pad10)") (class "Default")
      (node (ref "IC1") (pin "10") (pinfunction "TXON2_10") (pintype "output"))
    )
    (net (code "83") (name "unconnected-(IC1-TXON3-Pad16)") (class "Default")
      (node (ref "IC1") (pin "16") (pinfunction "TXON3_16") (pintype "output"))
    )
    (net (code "84") (name "unconnected-(IC1-TXOP2-Pad9)") (class "Default")
      (node (ref "IC1") (pin "9") (pinfunction "TXOP2_9") (pintype "output"))
    )
    (net (code "85") (name "unconnected-(IC1-TXOP3-Pad17)") (class "Default")
      (node (ref "IC1") (pin "17") (pinfunction "TXOP3_17") (pintype "output"))
    )
    (net (code "86") (name "unconnected-(IC1-XO-Pad39)") (class "Default")
      (node (ref "IC1") (pin "39") (pinfunction "XO_39") (pintype "output"))
    )
    (net (code "87") (name "unconnected-(IC2-COL-Pad27)") (class "Default")
      (node (ref "IC2") (pin "27") (pinfunction "COL_27") (pintype "bidirectional"))
    )
    (net (code "88") (name "unconnected-(IC2-RXC-Pad13)") (class "Default")
      (node (ref "IC2") (pin "13") (pinfunction "RXC_13") (pintype "bidirectional"))
    )
    (net (code "89") (name "unconnected-(IC2-RXD[3]{slash}CLK_CTL-Pad12)") (class "Default")
      (node (ref "IC2") (pin "12") (pinfunction "RXD[3]/CLK_CTL_12") (pintype "bidirectional"))
    )
    (net (code "90") (name "unconnected-(IC2-TXC-Pad15)") (class "Default")
      (node (ref "IC2") (pin "15") (pinfunction "TXC_15") (pintype "bidirectional"))
    )
    (net (code "91") (name "unconnected-(IC2-TXD[2]-Pad18)") (class "Default")
      (node (ref "IC2") (pin "18") (pinfunction "TXD[2]_18") (pintype "bidirectional"))
    )
    (net (code "92") (name "unconnected-(IC2-TXD[3]-Pad19)") (class "Default")
      (node (ref "IC2") (pin "19") (pinfunction "TXD[3]_19") (pintype "bidirectional"))
    )
    (net (code "93") (name "unconnected-(J1-NC-Pad7)") (class "Default")
      (node (ref "J1") (pin "7") (pinfunction "NC_7") (pintype "bidirectional"))
    )
    (net (code "94") (name "unconnected-(J1-YLW+-Pad9)") (class "Default")
      (node (ref "J1") (pin "9") (pinfunction "YLW+_9") (pintype "bidirectional"))
    )
    (net (code "95") (name "unconnected-(J1-YLW--Pad10)") (class "Default")
      (node (ref "J1") (pin "10") (pinfunction "YLW-_10") (pintype "bidirectional"))
    )
    (net (code "96") (name "unconnected-(J2-NC-Pad7)") (class "Default")
      (node (ref "J2") (pin "7") (pinfunction "NC_7") (pintype "bidirectional"))
    )
    (net (code "97") (name "unconnected-(J2-YLW+-Pad9)") (class "Default")
      (node (ref "J2") (pin "9") (pinfunction "YLW+_9") (pintype "bidirectional"))
    )
    (net (code "98") (name "unconnected-(J2-YLW--Pad10)") (class "Default")
      (node (ref "J2") (pin "10") (pinfunction "YLW-_10") (pintype "bidirectional"))
    )
    (net (code "99") (name "unconnected-(Q1-TS-Pad1)") (class "Default")
      (node (ref "Q1") (pin "1") (pinfunction "TS_1") (pintype "passive"))
    )
    (net (code "100") (name "unconnected-(Q2-TS-Pad1)") (class "Default")
      (node (ref "Q2") (pin "1") (pinfunction "TS_1") (pintype "passive"))
    )
    (net (code "101") (name "unconnected-(RN2-Pad1)") (class "Default")
      (node (ref "RN2") (pin "1") (pinfunction "1_1") (pintype "passive"))
    )
    (net (code "102") (name "unconnected-(RN2A-2-Pad8)") (class "Default")
      (node (ref "RN2") (pin "8") (pinfunction "2_8") (pintype "passive"))
    )
    (net (code "103") (name "unconnected-(RN3-Pad1)") (class "Default")
      (node (ref "RN3") (pin "1") (pinfunction "1_1") (pintype "passive"))
    )
    (net (code "104") (name "unconnected-(RN3A-2-Pad8)") (class "Default")
      (node (ref "RN3") (pin "8") (pinfunction "2_8") (pintype "passive"))
    )
  )
)
